# Power_Board_Control.net
KiCad netlist of a schematic drawn in Altium Designer
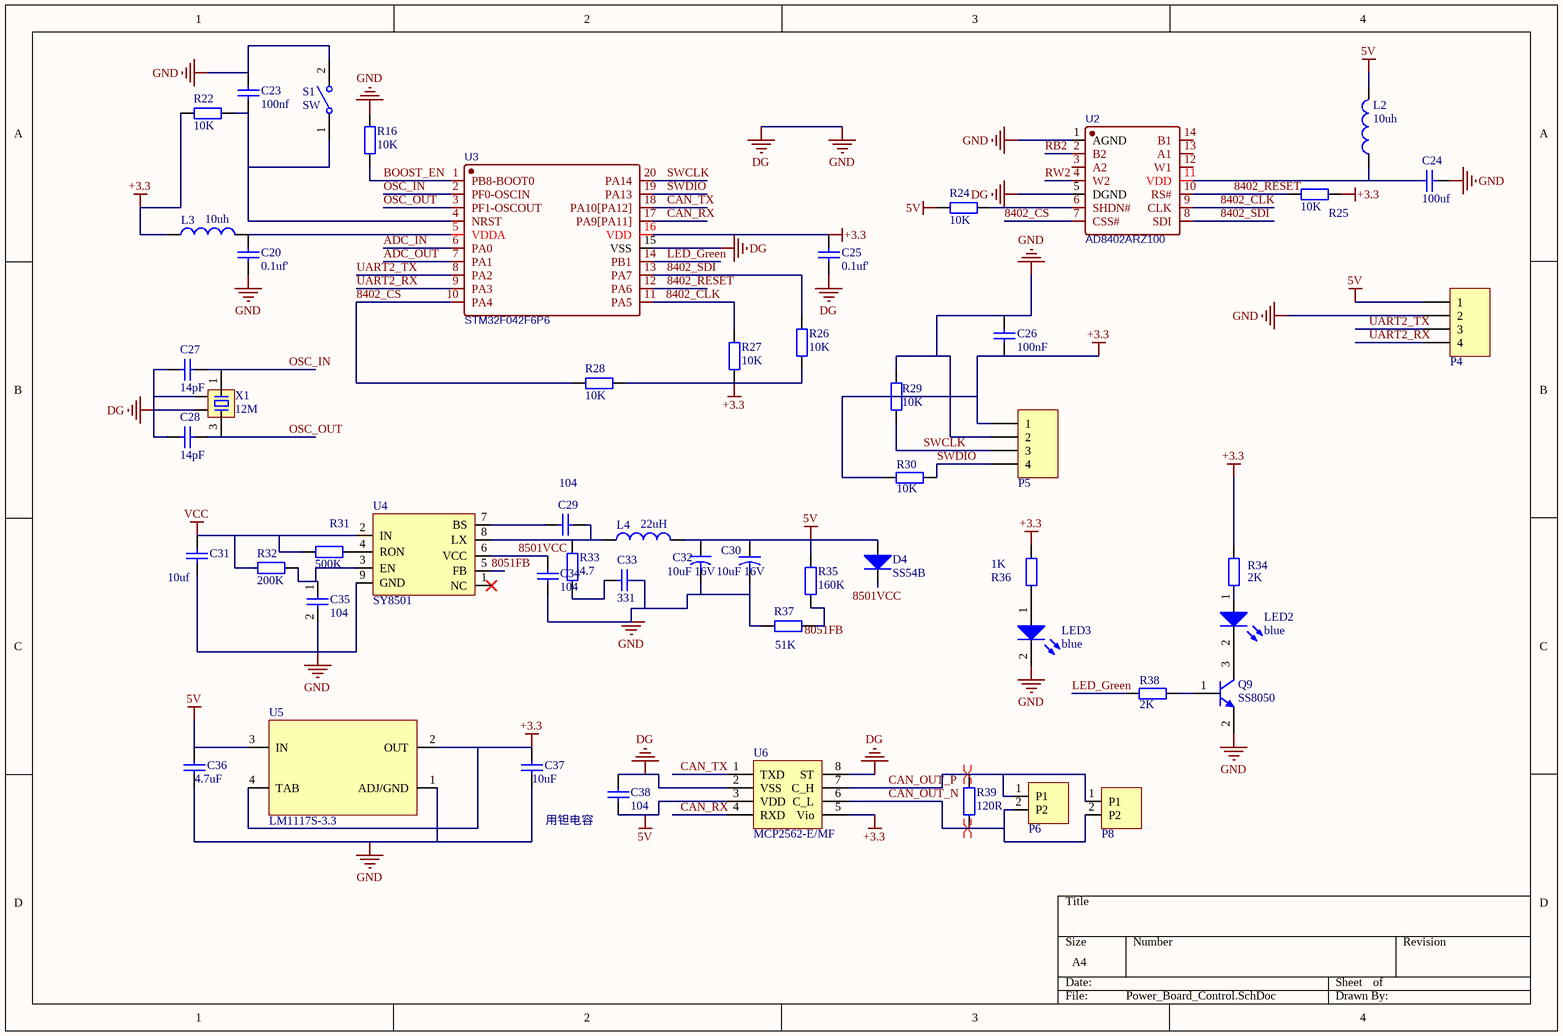
[diagram p0: Power_Board_Control.SchDoc]

(export (version "E")
  (design (tool "Eeschema 10.0.6"))
  (components
    (comp (ref "C20")
      (value "0.1uf'")
      (footprint "c0402")
      (description "无极性电容")
      (fields (field (name "Comment") "0.1uf") (field (name "PUBLISHER") "Altium Limited"))
      (libsource (lib "Fszhang") (part "Cap"))
    )
    (comp (ref "C23")
      (value "100nf")
      (footprint "c0402")
      (description "无极性电容")
      (fields (field (name "PUBLISHER") "Altium Limited"))
      (libsource (lib "Fszhang") (part "Cap"))
    )
    (comp (ref "C24")
      (value "100uf")
      (footprint "1210C")
      (description "无极性电容")
      (fields (field (name "PUBLISHER") "Altium Limited"))
      (libsource (lib "Fszhang") (part "Cap"))
    )
    (comp (ref "C25")
      (value "0.1uf'")
      (footprint "c0402")
      (description "无极性电容")
      (fields (field (name "PUBLISHER") "Altium Limited"))
      (libsource (lib "Fszhang") (part "Cap"))
    )
    (comp (ref "C26")
      (value "100nF")
      (footprint "c0402")
      (description "无极性电容")
      (fields (field (name "PUBLISHER") "Altium Limited"))
      (libsource (lib "Fszhang") (part "Cap"))
    )
    (comp (ref "C27")
      (value "14pF")
      (footprint "c0402")
      (description "无极性电容")
      (fields (field (name "Comment") "27pf") (field (name "PUBLISHER") "Altium Limited"))
      (libsource (lib "Fszhang") (part "Cap"))
    )
    (comp (ref "C28")
      (value "14pF")
      (footprint "c0402")
      (description "无极性电容")
      (fields (field (name "Comment") "27pf") (field (name "PUBLISHER") "Altium Limited"))
      (libsource (lib "Fszhang") (part "Cap"))
    )
    (comp (ref "C29")
      (value "104")
      (footprint "c0402")
      (description "无极性电容")
      (fields (field (name "PUBLISHER") "Altium Limited"))
      (libsource (lib "Fszhang") (part "Cap"))
    )
    (comp (ref "C30")
      (value "10uF 16V")
      (footprint "3216")
      (description "贴片电解")
      (fields (field (name "PUBLISHER") "Altium Limited"))
      (libsource (lib "Miscellaneous Devices") (part "Cap2"))
    )
    (comp (ref "C31")
      (value "10uf")
      (footprint "0805-1C")
      (description "无极性电容")
      (fields (field (name "PUBLISHER") "Altium Limited"))
      (libsource (lib "Fszhang") (part "Cap"))
    )
    (comp (ref "C32")
      (value "10uF 16V")
      (footprint "3216")
      (description "贴片电解")
      (fields (field (name "PUBLISHER") "Altium Limited"))
      (libsource (lib "Miscellaneous Devices") (part "Cap2"))
    )
    (comp (ref "C33")
      (value "331")
      (footprint "c0402")
      (description "无极性电容")
      (fields (field (name "PUBLISHER") "Altium Limited"))
      (libsource (lib "Fszhang") (part "Cap"))
    )
    (comp (ref "C34")
      (value "104")
      (footprint "c0402")
      (description "无极性电容")
      (fields (field (name "PUBLISHER") "Altium Limited"))
      (libsource (lib "Fszhang") (part "Cap"))
    )
    (comp (ref "C35")
      (value "104")
      (footprint "c0402")
      (description "贴片电容1206")
      (fields (field (name "C") "104"))
      (libsource (lib "原理图库") (part "CAP-W"))
    )
    (comp (ref "C36")
      (value "4.7uF")
      (footprint "0805-2")
      (description "无极性电容")
      (fields (field (name "Comment") "4.7uf") (field (name "PUBLISHER") "Altium Limited"))
      (libsource (lib "Fszhang") (part "Cap"))
    )
    (comp (ref "C37")
      (value "10uF")
      (footprint "3216")
      (description "无极性电容")
      (fields (field (name "Comment") "10uf") (field (name "PUBLISHER") "Altium Limited"))
      (libsource (lib "Fszhang") (part "Cap"))
    )
    (comp (ref "C38")
      (value "104")
      (footprint "c0402")
      (description "贴片电容")
      (libsource (lib "0.1 - 电阻-电容-电感-电位器") (part "C"))
    )
    (comp (ref "D4")
      (value "SS54B")
      (footprint "DO-214")
      (description "肖特基二极管")
      (fields (field (name "PUBLISHER") "Altium Limited"))
      (libsource (lib "Miscellaneous Devices") (part "Diode"))
    )
    (comp (ref "L2")
      (value "10uh")
      (footprint "l0805")
      (description "功率电感")
      (fields (field (name "PUBLISHER") "Altium Limited"))
      (libsource (lib "Miscellaneous Devices") (part "Inductor"))
    )
    (comp (ref "L3")
      (value "10uh")
      (footprint "l0805")
      (description "功率电感")
      (fields (field (name "PUBLISHER") "Altium Limited"))
      (libsource (lib "Miscellaneous Devices") (part "Inductor"))
    )
    (comp (ref "L4")
      (value "22uH")
      (footprint "CD54NP")
      (description "功率电感")
      (fields (field (name "PUBLISHER") "Altium Limited"))
      (libsource (lib "Miscellaneous Devices") (part "Inductor"))
    )
    (comp (ref "LED2")
      (value "LED_灯_黄")
      (footprint "led0805")
      (description "贴片LED")
      (fields (field (name "COLOR") "blue"))
      (libsource (lib "super_cap") (part "LED"))
    )
    (comp (ref "LED3")
      (value "LED_灯_黄")
      (footprint "led0805")
      (description "贴片LED")
      (fields (field (name "COLOR") "blue"))
      (libsource (lib "super_cap") (part "LED"))
    )
    (comp (ref "P4")
      (value "Header 4")
      (footprint "gh1.25 4p 立贴")
      (description "排针")
      (fields (field (name "PUBLISHER") "Altium Limited"))
      (libsource (lib "super_cap") (part "Header 4"))
    )
    (comp (ref "P5")
      (value "Header 4")
      (footprint "gh1.25 4p 立贴")
      (description "排针")
      (fields (field (name "PUBLISHER") "Altium Limited"))
      (libsource (lib "super_cap") (part "Header 4"))
    )
    (comp (ref "P6") (value "P2") (footprint "gh1.25") (libsource (lib "原理图库") (part "P2")))
    (comp (ref "P8") (value "P2") (footprint "gh1.25") (libsource (lib "原理图库") (part "P2")))
    (comp (ref "Q9")
      (value "SS8050")
      (footprint "SOT-23")
      (description "NPN贴片三极管")
      (fields (field (name "PUBLISHER") "Altium Limited"))
      (libsource (lib "fszhang") (part "SS8050"))
    )
    (comp (ref "R16")
      (value "10K")
      (footprint "r0402")
      (description "贴片电阻")
      (libsource (lib "super_cap") (part "R"))
    )
    (comp (ref "R22")
      (value "10K")
      (footprint "r0402")
      (description "贴片电阻")
      (libsource (lib "super_cap") (part "R"))
    )
    (comp (ref "R24")
      (value "10K")
      (footprint "r0402")
      (description "贴片电阻")
      (libsource (lib "super_cap") (part "R"))
    )
    (comp (ref "R25")
      (value "10K")
      (footprint "r0402")
      (description "贴片电阻")
      (libsource (lib "super_cap") (part "R"))
    )
    (comp (ref "R26")
      (value "10K")
      (footprint "r0402")
      (description "贴片电阻")
      (libsource (lib "super_cap") (part "R"))
    )
    (comp (ref "R27")
      (value "10K")
      (footprint "r0402")
      (description "贴片电阻")
      (libsource (lib "super_cap") (part "R"))
    )
    (comp (ref "R28")
      (value "10K")
      (footprint "r0402")
      (description "贴片电阻")
      (libsource (lib "super_cap") (part "R"))
    )
    (comp (ref "R29")
      (value "10K")
      (footprint "r0402")
      (description "贴片电阻")
      (fields (field (name "PUBLISHER") "Altium Limited"))
      (libsource (lib "") (part "Res1_2"))
    )
    (comp (ref "R30")
      (value "10K")
      (footprint "r0402")
      (description "贴片电阻")
      (fields (field (name "PUBLISHER") "Altium Limited"))
      (libsource (lib "") (part "Res1_1"))
    )
    (comp (ref "R31")
      (value "500K")
      (footprint "r0402")
      (description "贴片电阻")
      (libsource (lib "super_cap") (part "R"))
    )
    (comp (ref "R32")
      (value "200K")
      (footprint "r0402")
      (description "贴片电阻")
      (libsource (lib "super_cap") (part "R"))
    )
    (comp (ref "R33")
      (value "4.7")
      (footprint "r0402")
      (description "贴片电阻")
      (libsource (lib "super_cap") (part "R"))
    )
    (comp (ref "R34")
      (value "2K")
      (footprint "r0402")
      (description "贴片电阻")
      (fields (field (name "PUBLISHER") "Altium Limited"))
      (libsource (lib "") (part "Res1_2"))
    )
    (comp (ref "R35")
      (value "160K")
      (footprint "r0402")
      (description "贴片电阻")
      (libsource (lib "super_cap") (part "R"))
    )
    (comp (ref "R36")
      (value "1K")
      (footprint "r0402")
      (description "贴片电阻")
      (fields (field (name "PUBLISHER") "Altium Limited"))
      (libsource (lib "Fszhang") (part "Res1"))
    )
    (comp (ref "R37")
      (value "51K")
      (footprint "r0402")
      (description "贴片电阻")
      (libsource (lib "super_cap") (part "R"))
    )
    (comp (ref "R38")
      (value "2K")
      (footprint "r0402")
      (description "贴片电阻")
      (fields (field (name "PUBLISHER") "Altium Limited"))
      (libsource (lib "") (part "Res1_1"))
    )
    (comp (ref "R39")
      (value "120R")
      (footprint "r0402")
      (description "贴片电阻")
      (libsource (lib "0.1 - 电阻-电容-电感-电位器") (part "R"))
    )
    (comp (ref "S1") (value "SW") (footprint "KEY_SMD") (libsource (lib "super_cap") (part "SW")))
    (comp (ref "U2")
      (value "AD8402ARZ100")
      (footprint "SOIC14")
      (fields (field (name "BOM_SUPPLIER PART") "C652776") (field (name "CONTRIBUTOR") "LCSC"))
      (libsource (lib "ofq") (part "AD8402ARZ100"))
    )
    (comp (ref "U3")
      (value "STM32F042F6P6")
      (footprint "TSSOP-20")
      (fields (field (name "BOM_SUPPLIER PART") "C81000"))
      (libsource (lib "ofq") (part "STM32F042F6P6"))
    )
    (comp (ref "U4")
      (value "SY8501")
      (footprint "SO8E")
      (description "电源管理芯片")
      (libsource (lib "super_cap") (part "SY8501"))
    )
    (comp (ref "U5")
      (value "LM1117S-3.3")
      (footprint "sot-223")
      (libsource (lib "super_cap") (part "LM1117S-3.3"))
    )
    (comp (ref "U6") (value "MCP2562-E/MF") (footprint "LM358") (libsource (lib "原理图库") (part "TLP250")))
    (comp (ref "X1")
      (value "12M")
      (footprint "XTAL-3225")
      (description "4脚无源晶振")
      (libsource (lib "super_cap") (part "XTAL-4P"))
    )
  )
  (nets
    (net (code "1") (name "+3.3") (class "Default")
      (node (ref "C25") (pin "1") (pinfunction "1_1") (pintype "passive"))
      (node (ref "C26") (pin "2") (pinfunction "2_2") (pintype "passive"))
      (node (ref "C37") (pin "2") (pinfunction "2_2") (pintype "passive"))
      (node (ref "L3") (pin "1") (pinfunction "1_1") (pintype "passive"))
      (node (ref "P5") (pin "1") (pinfunction "1_1") (pintype "passive"))
      (node (ref "R22") (pin "1") (pinfunction "1_1") (pintype "passive"))
      (node (ref "R25") (pin "1") (pinfunction "1_1") (pintype "passive"))
      (node (ref "R26") (pin "2") (pinfunction "2_2") (pintype "passive"))
      (node (ref "R27") (pin "2") (pinfunction "2_2") (pintype "passive"))
      (node (ref "R28") (pin "2") (pinfunction "2_2") (pintype "passive"))
      (node (ref "R30") (pin "1") (pinfunction "1_1") (pintype "passive"))
      (node (ref "R34") (pin "1") (pinfunction "1_1") (pintype "passive"))
      (node (ref "R36") (pin "2") (pinfunction "2_2") (pintype "passive"))
      (node (ref "U3") (pin "16") (pinfunction "VDD_16") (pintype "passive"))
      (node (ref "U5") (pin "2") (pinfunction "OUT_2") (pintype "passive"))
      (node (ref "U5") (pin "4") (pinfunction "TAB_4") (pintype "passive"))
      (node (ref "U6") (pin "5") (pinfunction "Vio_5") (pintype "passive"))
    )
    (net (code "2") (name "/8051FB") (class "Default")
      (node (ref "R35") (pin "2") (pinfunction "2_2") (pintype "passive"))
      (node (ref "R37") (pin "2") (pinfunction "2_2") (pintype "passive"))
      (node (ref "U4") (pin "5") (pinfunction "FB_5") (pintype "passive"))
    )
    (net (code "3") (name "/8402_CLK") (class "Default")
      (node (ref "R27") (pin "1") (pinfunction "1_1") (pintype "passive"))
      (node (ref "U2") (pin "9") (pinfunction "CLK_9") (pintype "passive"))
      (node (ref "U3") (pin "11") (pinfunction "PA5_11") (pintype "passive"))
    )
    (net (code "4") (name "/8402_CS") (class "Default")
      (node (ref "R28") (pin "1") (pinfunction "1_1") (pintype "passive"))
      (node (ref "U2") (pin "7") (pinfunction "CSS#_7") (pintype "passive"))
      (node (ref "U3") (pin "10") (pinfunction "PA4_10") (pintype "passive"))
    )
    (net (code "5") (name "/8402_RESET") (class "Default")
      (node (ref "R25") (pin "2") (pinfunction "2_2") (pintype "passive"))
      (node (ref "U2") (pin "10") (pinfunction "RS#_10") (pintype "passive"))
      (node (ref "U3") (pin "12") (pinfunction "PA6_12") (pintype "passive"))
    )
    (net (code "6") (name "/8402_SDI") (class "Default")
      (node (ref "R26") (pin "1") (pinfunction "1_1") (pintype "passive"))
      (node (ref "U2") (pin "8") (pinfunction "SDI_8") (pintype "passive"))
      (node (ref "U3") (pin "13") (pinfunction "PA7_13") (pintype "passive"))
    )
    (net (code "7") (name "/8501VCC") (class "Default")
      (node (ref "C34") (pin "1") (pinfunction "1_1") (pintype "passive"))
      (node (ref "D4") (pin "2") (pinfunction "K_2") (pintype "passive"))
      (node (ref "U4") (pin "6") (pinfunction "VCC_6") (pintype "passive"))
    )
    (net (code "8") (name "/ADC_IN") (class "Default")
      (node (ref "U3") (pin "6") (pinfunction "PA0_6") (pintype "passive"))
    )
    (net (code "9") (name "/ADC_OUT") (class "Default")
      (node (ref "U3") (pin "7") (pinfunction "PA1_7") (pintype "passive"))
    )
    (net (code "10") (name "/BOOST_EN") (class "Default")
      (node (ref "R16") (pin "2") (pinfunction "2_2") (pintype "passive"))
      (node (ref "U3") (pin "1") (pinfunction "PB8-BOOT0_1") (pintype "passive"))
    )
    (net (code "11") (name "/CAN_OUT_N") (class "Default")
      (node (ref "P6") (pin "2") (pinfunction "P2_2") (pintype "passive"))
      (node (ref "P8") (pin "2") (pinfunction "P2_2") (pintype "passive"))
      (node (ref "R39") (pin "1") (pinfunction "1_1") (pintype "passive"))
      (node (ref "U6") (pin "6") (pinfunction "C_L_6") (pintype "passive"))
    )
    (net (code "12") (name "/CAN_OUT_P") (class "Default")
      (node (ref "P6") (pin "1") (pinfunction "P1_1") (pintype "passive"))
      (node (ref "P8") (pin "1") (pinfunction "P1_1") (pintype "passive"))
      (node (ref "R39") (pin "2") (pinfunction "2_2") (pintype "passive"))
      (node (ref "U6") (pin "7") (pinfunction "C_H_7") (pintype "passive"))
    )
    (net (code "13") (name "/CAN_RX") (class "Default")
      (node (ref "U3") (pin "17") (pinfunction "PA9[PA11]_17") (pintype "passive"))
      (node (ref "U6") (pin "4") (pinfunction "RXD_4") (pintype "passive"))
    )
    (net (code "14") (name "/CAN_TX") (class "Default")
      (node (ref "U3") (pin "18") (pinfunction "PA10[PA12]_18") (pintype "passive"))
      (node (ref "U6") (pin "1") (pinfunction "TXD_1") (pintype "passive"))
    )
    (net (code "15") (name "/LED_Green") (class "Default")
      (node (ref "R38") (pin "1") (pinfunction "1_1") (pintype "passive"))
      (node (ref "U3") (pin "14") (pinfunction "PB1_14") (pintype "passive"))
    )
    (net (code "16") (name "/OSC_IN") (class "Default")
      (node (ref "C27") (pin "1") (pinfunction "1_1") (pintype "passive"))
      (node (ref "U3") (pin "2") (pinfunction "PF0-OSCIN_2") (pintype "passive"))
      (node (ref "X1") (pin "1") (pinfunction "1_1") (pintype "passive"))
    )
    (net (code "17") (name "/OSC_OUT") (class "Default")
      (node (ref "C28") (pin "1") (pinfunction "1_1") (pintype "passive"))
      (node (ref "U3") (pin "3") (pinfunction "PF1-OSCOUT_3") (pintype "passive"))
      (node (ref "X1") (pin "3") (pinfunction "3_3") (pintype "passive"))
    )
    (net (code "18") (name "/RB2") (class "Default")
      (node (ref "U2") (pin "2") (pinfunction "B2_2") (pintype "passive"))
    )
    (net (code "19") (name "/RW2") (class "Default")
      (node (ref "U2") (pin "4") (pinfunction "W2_4") (pintype "passive"))
    )
    (net (code "20") (name "/SWCLK") (class "Default")
      (node (ref "P5") (pin "3") (pinfunction "3_3") (pintype "passive"))
      (node (ref "R29") (pin "2") (pinfunction "2_2") (pintype "passive"))
      (node (ref "U3") (pin "20") (pinfunction "PA14_20") (pintype "passive"))
    )
    (net (code "21") (name "/SWDIO") (class "Default")
      (node (ref "P5") (pin "4") (pinfunction "4_4") (pintype "passive"))
      (node (ref "R30") (pin "2") (pinfunction "2_2") (pintype "passive"))
      (node (ref "U3") (pin "19") (pinfunction "PA13_19") (pintype "passive"))
    )
    (net (code "22") (name "/UART2_RX") (class "Default")
      (node (ref "P4") (pin "4") (pinfunction "4_4") (pintype "passive"))
      (node (ref "U3") (pin "9") (pinfunction "PA3_9") (pintype "passive"))
    )
    (net (code "23") (name "/UART2_TX") (class "Default")
      (node (ref "P4") (pin "3") (pinfunction "3_3") (pintype "passive"))
      (node (ref "U3") (pin "8") (pinfunction "PA2_8") (pintype "passive"))
    )
    (net (code "24") (name "5V") (class "Default")
      (node (ref "C30") (pin "1") (pinfunction "1_1") (pintype "passive"))
      (node (ref "C32") (pin "1") (pinfunction "1_1") (pintype "passive"))
      (node (ref "C36") (pin "2") (pinfunction "2_2") (pintype "passive"))
      (node (ref "C38") (pin "2") (pinfunction "2_2") (pintype "passive"))
      (node (ref "D4") (pin "1") (pinfunction "A_1") (pintype "passive"))
      (node (ref "L2") (pin "2") (pinfunction "2_2") (pintype "passive"))
      (node (ref "L4") (pin "2") (pinfunction "2_2") (pintype "passive"))
      (node (ref "P4") (pin "1") (pinfunction "1_1") (pintype "passive"))
      (node (ref "R24") (pin "2") (pinfunction "2_2") (pintype "passive"))
      (node (ref "R35") (pin "1") (pinfunction "1_1") (pintype "passive"))
      (node (ref "U5") (pin "3") (pinfunction "IN_3") (pintype "passive"))
      (node (ref "U6") (pin "3") (pinfunction "VDD_3") (pintype "passive"))
    )
    (net (code "25") (name "DG") (class "Default")
      (node (ref "C20") (pin "2") (pinfunction "2_2") (pintype "passive"))
      (node (ref "C23") (pin "1") (pinfunction "1_1") (pintype "passive"))
      (node (ref "C24") (pin "1") (pinfunction "1_1") (pintype "passive"))
      (node (ref "C25") (pin "2") (pinfunction "2_2") (pintype "passive"))
      (node (ref "C26") (pin "1") (pinfunction "1_1") (pintype "passive"))
      (node (ref "C27") (pin "2") (pinfunction "2_2") (pintype "passive"))
      (node (ref "C28") (pin "2") (pinfunction "2_2") (pintype "passive"))
      (node (ref "C30") (pin "2") (pinfunction "2_2") (pintype "passive"))
      (node (ref "C31") (pin "2") (pinfunction "2_2") (pintype "passive"))
      (node (ref "C32") (pin "2") (pinfunction "2_2") (pintype "passive"))
      (node (ref "C33") (pin "1") (pinfunction "1_1") (pintype "passive"))
      (node (ref "C34") (pin "2") (pinfunction "2_2") (pintype "passive"))
      (node (ref "C35") (pin "2") (pinfunction "2_2") (pintype "passive"))
      (node (ref "C36") (pin "1") (pinfunction "1_1") (pintype "passive"))
      (node (ref "C37") (pin "1") (pinfunction "1_1") (pintype "passive"))
      (node (ref "C38") (pin "1") (pinfunction "1_1") (pintype "passive"))
      (node (ref "LED3") (pin "2") (pinfunction "K_2") (pintype "passive"))
      (node (ref "P4") (pin "2") (pinfunction "2_2") (pintype "passive"))
      (node (ref "P5") (pin "2") (pinfunction "2_2") (pintype "passive"))
      (node (ref "Q9") (pin "2") (pinfunction "E_2") (pintype "passive"))
      (node (ref "R16") (pin "1") (pinfunction "1_1") (pintype "passive"))
      (node (ref "R29") (pin "1") (pinfunction "1_1") (pintype "passive"))
      (node (ref "R37") (pin "1") (pinfunction "1_1") (pintype "passive"))
      (node (ref "S1") (pin "2") (pinfunction "NO_2") (pintype "passive"))
      (node (ref "U2") (pin "1") (pinfunction "AGND_1") (pintype "passive"))
      (node (ref "U2") (pin "5") (pinfunction "DGND_5") (pintype "passive"))
      (node (ref "U3") (pin "15") (pinfunction "VSS_15") (pintype "passive"))
      (node (ref "U4") (pin "9") (pinfunction "GND_9") (pintype "passive"))
      (node (ref "U5") (pin "1") (pinfunction "ADJ/GND_1") (pintype "passive"))
      (node (ref "U6") (pin "2") (pinfunction "VSS_2") (pintype "passive"))
      (node (ref "U6") (pin "8") (pinfunction "ST_8") (pintype "passive"))
      (node (ref "X1") (pin "2") (pinfunction "2_2") (pintype "passive"))
      (node (ref "X1") (pin "4") (pinfunction "4_4") (pintype "passive"))
    )
    (net (code "26") (name "Net-(C33-Pad2)") (class "Default")
      (node (ref "C33") (pin "2") (pinfunction "2_2") (pintype "passive"))
      (node (ref "R33") (pin "2") (pinfunction "2_2") (pintype "passive"))
    )
    (net (code "27") (name "Net-(LED2-A)") (class "Default")
      (node (ref "LED2") (pin "1") (pinfunction "A_1") (pintype "passive"))
      (node (ref "R34") (pin "2") (pinfunction "2_2") (pintype "passive"))
    )
    (net (code "28") (name "Net-(LED2-K)") (class "Default")
      (node (ref "LED2") (pin "2") (pinfunction "K_2") (pintype "passive"))
      (node (ref "Q9") (pin "3") (pinfunction "C_3") (pintype "passive"))
    )
    (net (code "29") (name "Net-(LED3-A)") (class "Default")
      (node (ref "LED3") (pin "1") (pinfunction "A_1") (pintype "passive"))
      (node (ref "R36") (pin "1") (pinfunction "1_1") (pintype "passive"))
    )
    (net (code "30") (name "Net-(Q9-B)") (class "Default")
      (node (ref "Q9") (pin "1") (pinfunction "B_1") (pintype "passive"))
      (node (ref "R38") (pin "2") (pinfunction "2_2") (pintype "passive"))
    )
    (net (code "31") (name "Net-(S1-COMMON)") (class "Default")
      (node (ref "C23") (pin "2") (pinfunction "2_2") (pintype "passive"))
      (node (ref "R22") (pin "2") (pinfunction "2_2") (pintype "passive"))
      (node (ref "S1") (pin "1") (pinfunction "COMMON_1") (pintype "passive"))
      (node (ref "U3") (pin "4") (pinfunction "NRST_4") (pintype "passive"))
    )
    (net (code "32") (name "Net-(U2-SHDN#)") (class "Default")
      (node (ref "R24") (pin "1") (pinfunction "1_1") (pintype "passive"))
      (node (ref "U2") (pin "6") (pinfunction "SHDN#_6") (pintype "passive"))
    )
    (net (code "33") (name "Net-(U2-VDD)") (class "Default")
      (node (ref "C24") (pin "2") (pinfunction "2_2") (pintype "passive"))
      (node (ref "L2") (pin "1") (pinfunction "1_1") (pintype "passive"))
      (node (ref "U2") (pin "11") (pinfunction "VDD_11") (pintype "passive"))
    )
    (net (code "34") (name "Net-(U3-VDDA)") (class "Default")
      (node (ref "C20") (pin "1") (pinfunction "1_1") (pintype "passive"))
      (node (ref "L3") (pin "2") (pinfunction "2_2") (pintype "passive"))
      (node (ref "U3") (pin "5") (pinfunction "VDDA_5") (pintype "passive"))
    )
    (net (code "35") (name "Net-(U4-BS)") (class "Default")
      (node (ref "C29") (pin "2") (pinfunction "2_2") (pintype "passive"))
      (node (ref "U4") (pin "7") (pinfunction "BS_7") (pintype "passive"))
    )
    (net (code "36") (name "Net-(U4-EN)") (class "Default")
      (node (ref "C35") (pin "1") (pinfunction "1_1") (pintype "passive"))
      (node (ref "R32") (pin "1") (pinfunction "1_1") (pintype "passive"))
      (node (ref "U4") (pin "3") (pinfunction "EN_3") (pintype "passive"))
    )
    (net (code "37") (name "Net-(U4-LX)") (class "Default")
      (node (ref "C29") (pin "1") (pinfunction "1_1") (pintype "passive"))
      (node (ref "L4") (pin "1") (pinfunction "1_1") (pintype "passive"))
      (node (ref "R33") (pin "1") (pinfunction "1_1") (pintype "passive"))
      (node (ref "U4") (pin "8") (pinfunction "LX_8") (pintype "passive"))
    )
    (net (code "38") (name "Net-(U4-RON)") (class "Default")
      (node (ref "R31") (pin "1") (pinfunction "1_1") (pintype "passive"))
      (node (ref "U4") (pin "4") (pinfunction "RON_4") (pintype "passive"))
    )
    (net (code "39") (name "VCC") (class "Default")
      (node (ref "C31") (pin "1") (pinfunction "1_1") (pintype "passive"))
      (node (ref "R31") (pin "2") (pinfunction "2_2") (pintype "passive"))
      (node (ref "R32") (pin "2") (pinfunction "2_2") (pintype "passive"))
      (node (ref "U4") (pin "2") (pinfunction "IN_2") (pintype "passive"))
    )
    (net (code "40") (name "unconnected-(U2-A1-Pad13)") (class "Default")
      (node (ref "U2") (pin "13") (pinfunction "A1_13") (pintype "passive"))
    )
    (net (code "41") (name "unconnected-(U2-A2-Pad3)") (class "Default")
      (node (ref "U2") (pin "3") (pinfunction "A2_3") (pintype "passive"))
    )
    (net (code "42") (name "unconnected-(U2-B1-Pad14)") (class "Default")
      (node (ref "U2") (pin "14") (pinfunction "B1_14") (pintype "passive"))
    )
    (net (code "43") (name "unconnected-(U2-W1-Pad12)") (class "Default")
      (node (ref "U2") (pin "12") (pinfunction "W1_12") (pintype "passive"))
    )
    (net (code "44") (name "unconnected-(U4-NC-Pad1)") (class "Default")
      (node (ref "U4") (pin "1") (pinfunction "NC_1") (pintype "passive+no_connect"))
    )
  )
)
